# MainSheet.net
KiCad netlist of a schematic drawn in Altium Designer
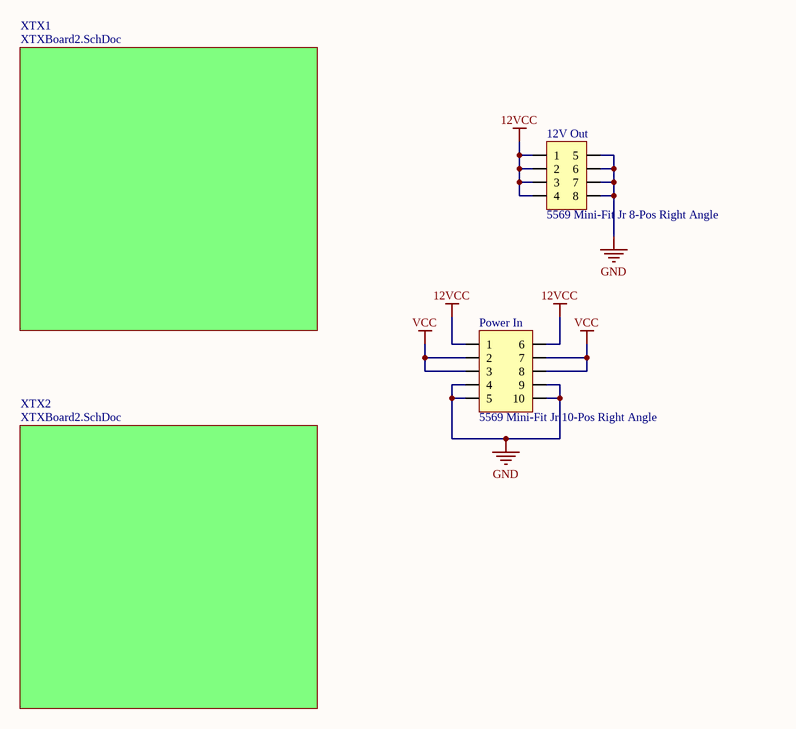
[diagram p0: MainSheet.SchDoc]

(export (version "E")
  (design (tool "Eeschema 10.0.6"))
  (components
    (comp (ref "12V Out")
      (value "5569 Mini-Fit Jr 8-Pos Right Angle")
      (footprint "MolexConnectors:8-POS 5569 Mini-Fit Jr 2")
      (libsource (lib "Molex") (part "5569 Mini-Fit Jr 8-Pos Right Angle"))
    )
    (comp (ref "Power In")
      (value "5569 Mini-Fit Jr 10-Pos Right Angle")
      (footprint "MolexConnectors:10-Pos 5569 Mini-Fit Jr 2")
      (libsource (lib "Molex") (part "5569 Mini-Fit Jr 10-Pos Right Angle"))
    )
  )
  (nets
    (net (code "1") (name "12VCC") (class "Default")
      (node (ref "12V Out") (pin "1") (pinfunction "1_1") (pintype "passive"))
      (node (ref "12V Out") (pin "2") (pinfunction "2_2") (pintype "passive"))
      (node (ref "12V Out") (pin "3") (pinfunction "3_3") (pintype "passive"))
      (node (ref "12V Out") (pin "4") (pinfunction "4_4") (pintype "passive"))
      (node (ref "Power In") (pin "1") (pinfunction "1_1") (pintype "passive"))
      (node (ref "Power In") (pin "6") (pinfunction "6_6") (pintype "passive"))
    )
    (net (code "2") (name "GND") (class "Default")
      (node (ref "12V Out") (pin "5") (pinfunction "5_5") (pintype "passive"))
      (node (ref "12V Out") (pin "6") (pinfunction "6_6") (pintype "passive"))
      (node (ref "12V Out") (pin "7") (pinfunction "7_7") (pintype "passive"))
      (node (ref "12V Out") (pin "8") (pinfunction "8_8") (pintype "passive"))
      (node (ref "Power In") (pin "10") (pinfunction "10_10") (pintype "passive"))
      (node (ref "Power In") (pin "4") (pinfunction "4_4") (pintype "passive"))
      (node (ref "Power In") (pin "5") (pinfunction "5_5") (pintype "passive"))
      (node (ref "Power In") (pin "9") (pinfunction "9_9") (pintype "passive"))
    )
    (net (code "3") (name "VCC") (class "Default")
      (node (ref "Power In") (pin "2") (pinfunction "2_2") (pintype "passive"))
      (node (ref "Power In") (pin "3") (pinfunction "3_3") (pintype "passive"))
      (node (ref "Power In") (pin "7") (pinfunction "7_7") (pintype "passive"))
      (node (ref "Power In") (pin "8") (pinfunction "8_8") (pintype "passive"))
    )
  )
)
